# Enclosure_Control.net
KiCad netlist of a schematic drawn in EAGLE
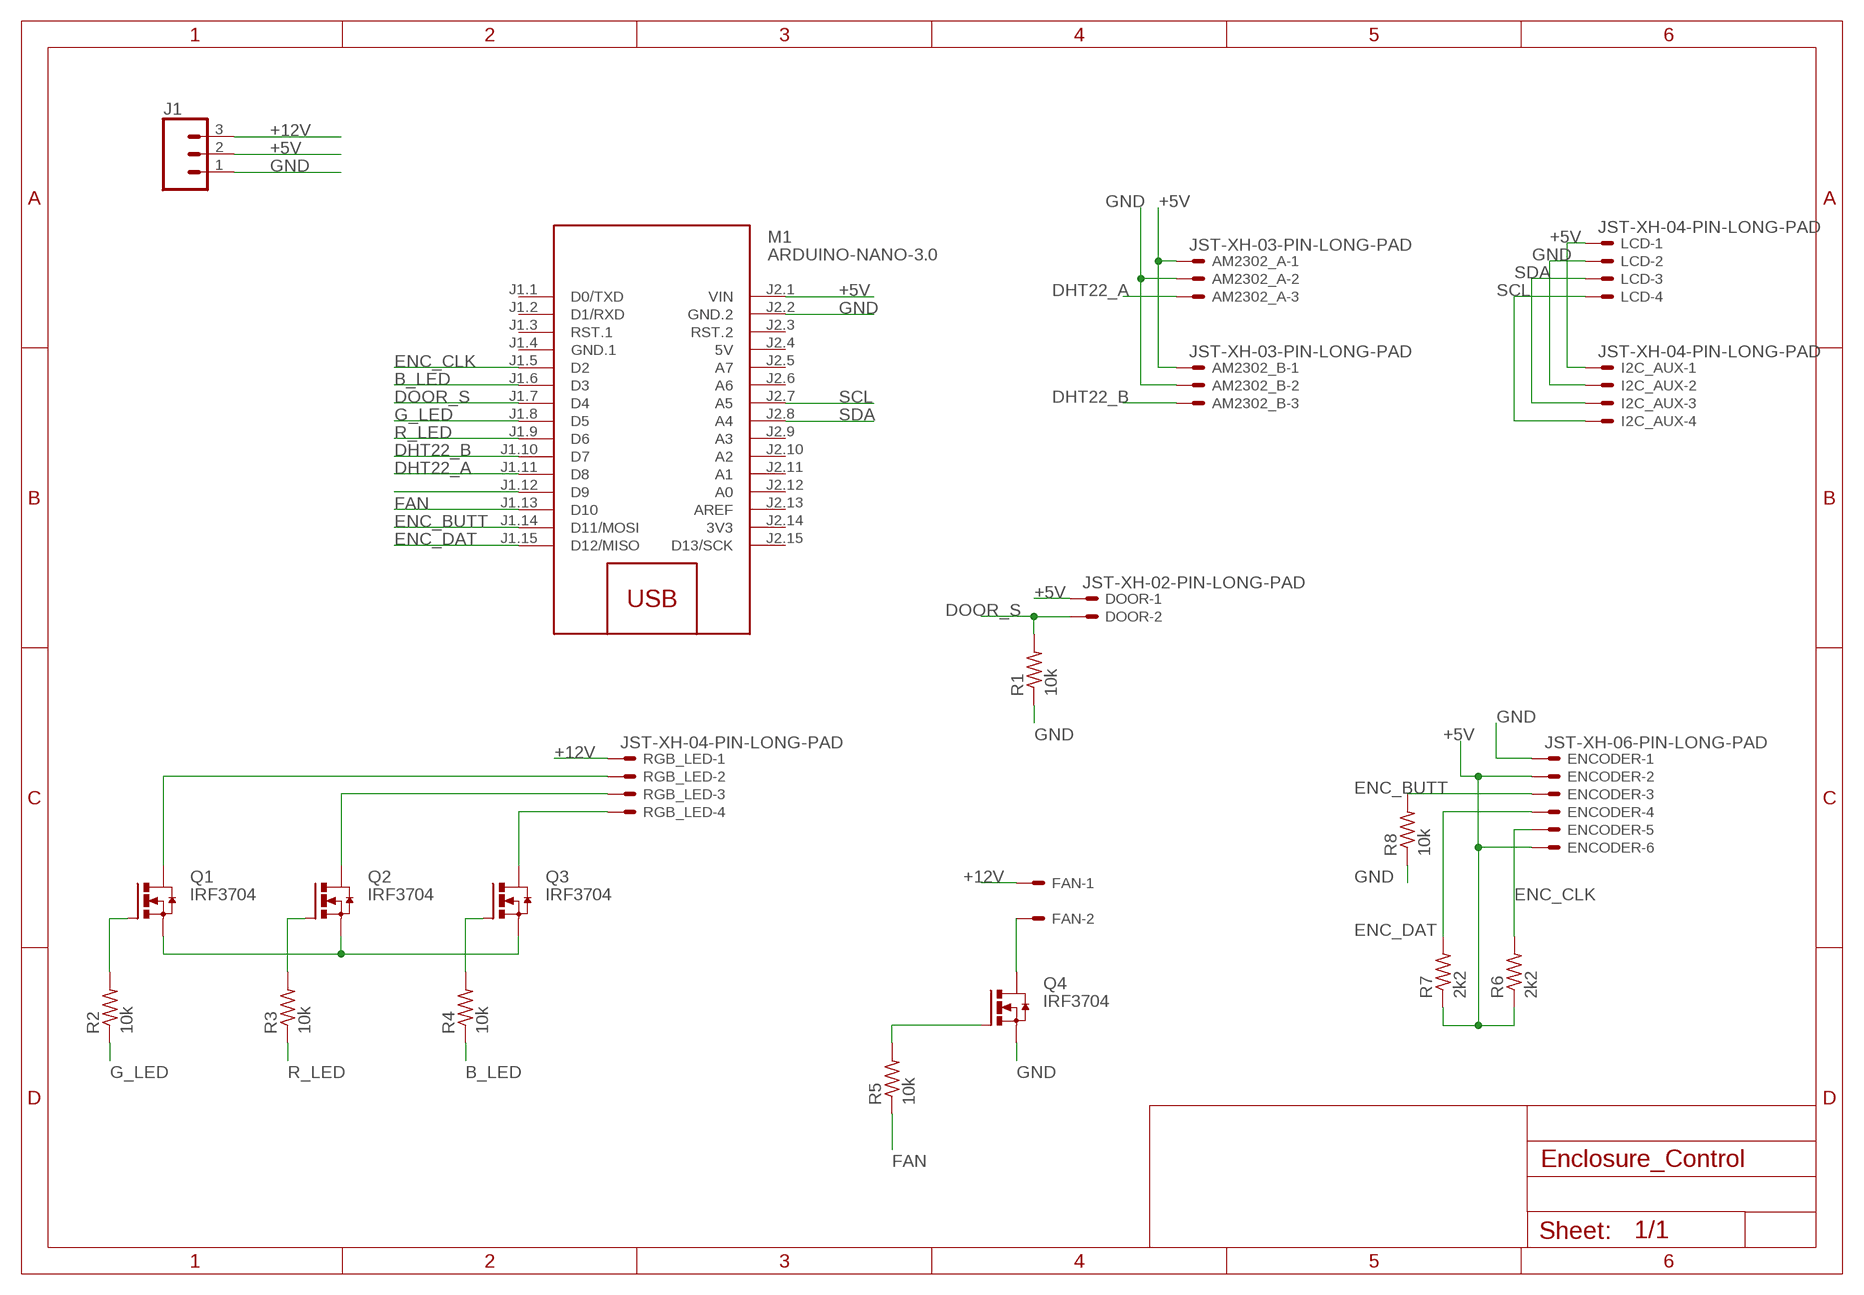
[diagram p0: schematic, sheet 1]

(export (version "E")
  (design (tool "Eeschema 10.0.6"))
  (components
    (comp (ref "AM2302_A")
      (value "JST-XH-03-PIN-LONG-PAD")
      (footprint "eagle-import:JST-XH-03-PACKAGE-LONG-PAD")
      (libsource (lib "eagle-import") (part "JST-XH-03-PIN-LONG-PAD"))
    )
    (comp (ref "AM2302_B")
      (value "JST-XH-03-PIN-LONG-PAD")
      (footprint "eagle-import:JST-XH-03-PACKAGE-LONG-PAD")
      (libsource (lib "eagle-import") (part "JST-XH-03-PIN-LONG-PAD"))
    )
    (comp (ref "DOOR")
      (value "JST-XH-02-PIN-LONG-PAD")
      (footprint "eagle-import:JST-XH-02-PACKAGE-LONG-PAD")
      (libsource (lib "eagle-import") (part "JST-XH-02-PIN-LONG-PAD"))
    )
    (comp (ref "ENCODER")
      (value "JST-XH-06-PIN-LONG-PAD")
      (footprint "eagle-import:JST-XH-06-PACKAGE-LONG-PAD")
      (libsource (lib "eagle-import") (part "JST-XH-06-PIN-LONG-PAD"))
    )
    (comp (ref "FAN")
      (value "KK-156-2")
      (footprint "eagle-import:KK-156-2")
      (fields (field (name "MF") "MOLEX"))
      (libsource (lib "eagle-import") (part "KK-156-2"))
    )
    (comp (ref "I2C_AUX")
      (value "JST-XH-04-PIN-LONG-PAD")
      (footprint "eagle-import:JST-XH-04-PACKAGE-LONG-PAD")
      (libsource (lib "eagle-import") (part "JST-XH-04-PIN-LONG-PAD"))
    )
    (comp (ref "J1")
      (value "CONN_03SCREW-NS")
      (footprint "eagle-import:SCREWTERMINAL-3.5MM-3-NS")
      (libsource (lib "eagle-import") (part "CONN_03SCREW-NS"))
    )
    (comp (ref "LCD")
      (value "JST-XH-04-PIN-LONG-PAD")
      (footprint "eagle-import:JST-XH-04-PACKAGE-LONG-PAD")
      (libsource (lib "eagle-import") (part "JST-XH-04-PIN-LONG-PAD"))
    )
    (comp (ref "M1")
      (value "ARDUINO-NANO-3.0")
      (footprint "eagle-import:ARDUINO-NANO-3.0")
      (libsource (lib "eagle-import") (part "ARDUINO-NANO-3.0"))
    )
    (comp (ref "Q1")
      (value "IRF3704")
      (footprint "eagle-import:TO220AH")
      (libsource (lib "eagle-import") (part "IRF3704"))
    )
    (comp (ref "Q2")
      (value "IRF3704")
      (footprint "eagle-import:TO220AH")
      (libsource (lib "eagle-import") (part "IRF3704"))
    )
    (comp (ref "Q3")
      (value "IRF3704")
      (footprint "eagle-import:TO220AH")
      (libsource (lib "eagle-import") (part "IRF3704"))
    )
    (comp (ref "Q4")
      (value "IRF3704")
      (footprint "eagle-import:TO220AH")
      (libsource (lib "eagle-import") (part "IRF3704"))
    )
    (comp (ref "R1")
      (value "10k")
      (footprint "eagle-import:0309_12")
      (libsource (lib "eagle-import") (part "R-US_0309/12"))
    )
    (comp (ref "R2")
      (value "10k")
      (footprint "eagle-import:0309_12")
      (libsource (lib "eagle-import") (part "R-US_0309/12"))
    )
    (comp (ref "R3")
      (value "10k")
      (footprint "eagle-import:0309_12")
      (libsource (lib "eagle-import") (part "R-US_0309/12"))
    )
    (comp (ref "R4")
      (value "10k")
      (footprint "eagle-import:0309_12")
      (libsource (lib "eagle-import") (part "R-US_0309/12"))
    )
    (comp (ref "R5")
      (value "10k")
      (footprint "eagle-import:0309_12")
      (libsource (lib "eagle-import") (part "R-US_0309/12"))
    )
    (comp (ref "R6")
      (value "2k2")
      (footprint "eagle-import:0309_12")
      (libsource (lib "eagle-import") (part "R-US_0309/12"))
    )
    (comp (ref "R7")
      (value "2k2")
      (footprint "eagle-import:0309_12")
      (libsource (lib "eagle-import") (part "R-US_0309/12"))
    )
    (comp (ref "R8")
      (value "10k")
      (footprint "eagle-import:0309_12")
      (libsource (lib "eagle-import") (part "R-US_0309/12"))
    )
    (comp (ref "RGB_LED")
      (value "JST-XH-04-PIN-LONG-PAD")
      (footprint "eagle-import:JST-XH-04-PACKAGE-LONG-PAD")
      (libsource (lib "eagle-import") (part "JST-XH-04-PIN-LONG-PAD"))
    )
  )
  (nets
    (net (code "1") (name "/+5V") (class "Default")
      (node (ref "AM2302_A") (pin "1") (pinfunction "S_1") (pintype "passive"))
      (node (ref "AM2302_B") (pin "1") (pinfunction "S_1") (pintype "passive"))
      (node (ref "DOOR") (pin "1") (pinfunction "S_1") (pintype "passive"))
      (node (ref "ENCODER") (pin "2") (pinfunction "S_2") (pintype "passive"))
      (node (ref "ENCODER") (pin "6") (pinfunction "S_6") (pintype "passive"))
      (node (ref "I2C_AUX") (pin "1") (pinfunction "S_1") (pintype "passive"))
      (node (ref "J1") (pin "2") (pinfunction "2_2") (pintype "passive"))
      (node (ref "LCD") (pin "1") (pinfunction "S_1") (pintype "passive"))
      (node (ref "M1") (pin "J2.1") (pinfunction "VIN_J2.1") (pintype "power_in"))
      (node (ref "R6") (pin "1") (pinfunction "1_1") (pintype "passive"))
      (node (ref "R7") (pin "1") (pinfunction "1_1") (pintype "passive"))
    )
    (net (code "2") (name "/+12V") (class "Default")
      (node (ref "FAN") (pin "1") (pinfunction "S_1") (pintype "passive"))
      (node (ref "J1") (pin "3") (pinfunction "3_3") (pintype "passive"))
      (node (ref "RGB_LED") (pin "1") (pinfunction "S_1") (pintype "passive"))
    )
    (net (code "3") (name "/3V3") (class "Default")
      (node (ref "M1") (pin "J2.14") (pinfunction "3V3_J2.14") (pintype "power_in"))
    )
    (net (code "4") (name "/5V") (class "Default")
      (node (ref "M1") (pin "J2.4") (pinfunction "5V_J2.4") (pintype "power_in"))
    )
    (net (code "5") (name "/B_LED") (class "Default")
      (node (ref "M1") (pin "J1.6") (pinfunction "D3_J1.6") (pintype "bidirectional"))
      (node (ref "R4") (pin "1") (pinfunction "1_1") (pintype "passive"))
    )
    (net (code "6") (name "/DHT22_A") (class "Default")
      (node (ref "AM2302_A") (pin "3") (pinfunction "S_3") (pintype "passive"))
      (node (ref "M1") (pin "J1.11") (pinfunction "D8_J1.11") (pintype "bidirectional"))
    )
    (net (code "7") (name "/DHT22_B") (class "Default")
      (node (ref "AM2302_B") (pin "3") (pinfunction "S_3") (pintype "passive"))
      (node (ref "M1") (pin "J1.10") (pinfunction "D7_J1.10") (pintype "bidirectional"))
    )
    (net (code "8") (name "/DOOR_S") (class "Default")
      (node (ref "DOOR") (pin "2") (pinfunction "S_2") (pintype "passive"))
      (node (ref "M1") (pin "J1.7") (pinfunction "D4_J1.7") (pintype "bidirectional"))
      (node (ref "R1") (pin "2") (pinfunction "2_2") (pintype "passive"))
    )
    (net (code "9") (name "/ENC_BUTT") (class "Default")
      (node (ref "ENCODER") (pin "3") (pinfunction "S_3") (pintype "passive"))
      (node (ref "M1") (pin "J1.14") (pinfunction "D11/MOSI_J1.14") (pintype "bidirectional"))
      (node (ref "R8") (pin "2") (pinfunction "2_2") (pintype "passive"))
    )
    (net (code "10") (name "/ENC_CLK") (class "Default")
      (node (ref "ENCODER") (pin "5") (pinfunction "S_5") (pintype "passive"))
      (node (ref "M1") (pin "J1.5") (pinfunction "D2_J1.5") (pintype "bidirectional"))
      (node (ref "R6") (pin "2") (pinfunction "2_2") (pintype "passive"))
    )
    (net (code "11") (name "/ENC_DAT") (class "Default")
      (node (ref "ENCODER") (pin "4") (pinfunction "S_4") (pintype "passive"))
      (node (ref "M1") (pin "J1.15") (pinfunction "D12/MISO_J1.15") (pintype "bidirectional"))
      (node (ref "R7") (pin "2") (pinfunction "2_2") (pintype "passive"))
    )
    (net (code "12") (name "/FAN") (class "Default")
      (node (ref "M1") (pin "J1.13") (pinfunction "D10_J1.13") (pintype "bidirectional"))
      (node (ref "R5") (pin "1") (pinfunction "1_1") (pintype "passive"))
    )
    (net (code "13") (name "/GND") (class "Default")
      (node (ref "AM2302_A") (pin "2") (pinfunction "S_2") (pintype "passive"))
      (node (ref "AM2302_B") (pin "2") (pinfunction "S_2") (pintype "passive"))
      (node (ref "ENCODER") (pin "1") (pinfunction "S_1") (pintype "passive"))
      (node (ref "I2C_AUX") (pin "2") (pinfunction "S_2") (pintype "passive"))
      (node (ref "J1") (pin "1") (pinfunction "1_1") (pintype "passive"))
      (node (ref "LCD") (pin "2") (pinfunction "S_2") (pintype "passive"))
      (node (ref "M1") (pin "J2.2") (pinfunction "GND.2_J2.2") (pintype "power_in"))
      (node (ref "Q4") (pin "E") (pinfunction "S_E") (pintype "passive"))
      (node (ref "R1") (pin "1") (pinfunction "1_1") (pintype "passive"))
      (node (ref "R8") (pin "1") (pinfunction "1_1") (pintype "passive"))
    )
    (net (code "14") (name "/GND.1") (class "Default")
      (node (ref "M1") (pin "J1.4") (pinfunction "GND.1_J1.4") (pintype "power_in"))
    )
    (net (code "15") (name "/G_LED") (class "Default")
      (node (ref "M1") (pin "J1.8") (pinfunction "D5_J1.8") (pintype "bidirectional"))
      (node (ref "R2") (pin "1") (pinfunction "1_1") (pintype "passive"))
    )
    (net (code "16") (name "/R_LED") (class "Default")
      (node (ref "M1") (pin "J1.9") (pinfunction "D6_J1.9") (pintype "bidirectional"))
      (node (ref "R3") (pin "1") (pinfunction "1_1") (pintype "passive"))
    )
    (net (code "17") (name "/SCL") (class "Default")
      (node (ref "I2C_AUX") (pin "4") (pinfunction "S_4") (pintype "passive"))
      (node (ref "LCD") (pin "4") (pinfunction "S_4") (pintype "passive"))
      (node (ref "M1") (pin "J2.7") (pinfunction "A5_J2.7") (pintype "bidirectional"))
    )
    (net (code "18") (name "/SDA") (class "Default")
      (node (ref "I2C_AUX") (pin "3") (pinfunction "S_3") (pintype "passive"))
      (node (ref "LCD") (pin "3") (pinfunction "S_3") (pintype "passive"))
      (node (ref "M1") (pin "J2.8") (pinfunction "A4_J2.8") (pintype "bidirectional"))
    )
    (net (code "19") (name "Net-(FANB-S)") (class "Default")
      (node (ref "FAN") (pin "2") (pinfunction "S_2") (pintype "passive"))
      (node (ref "Q4") (pin "C") (pinfunction "D_C") (pintype "passive"))
    )
    (net (code "20") (name "Net-(Q1-D)") (class "Default")
      (node (ref "Q1") (pin "C") (pinfunction "D_C") (pintype "passive"))
      (node (ref "RGB_LED") (pin "2") (pinfunction "S_2") (pintype "passive"))
    )
    (net (code "21") (name "Net-(Q1-G)") (class "Default")
      (node (ref "Q1") (pin "B") (pinfunction "G_B") (pintype "passive"))
      (node (ref "R2") (pin "2") (pinfunction "2_2") (pintype "passive"))
    )
    (net (code "22") (name "Net-(Q1-S)") (class "Default")
      (node (ref "Q1") (pin "E") (pinfunction "S_E") (pintype "passive"))
      (node (ref "Q2") (pin "E") (pinfunction "S_E") (pintype "passive"))
      (node (ref "Q3") (pin "E") (pinfunction "S_E") (pintype "passive"))
    )
    (net (code "23") (name "Net-(Q2-D)") (class "Default")
      (node (ref "Q2") (pin "C") (pinfunction "D_C") (pintype "passive"))
      (node (ref "RGB_LED") (pin "3") (pinfunction "S_3") (pintype "passive"))
    )
    (net (code "24") (name "Net-(Q2-G)") (class "Default")
      (node (ref "Q2") (pin "B") (pinfunction "G_B") (pintype "passive"))
      (node (ref "R3") (pin "2") (pinfunction "2_2") (pintype "passive"))
    )
    (net (code "25") (name "Net-(Q3-D)") (class "Default")
      (node (ref "Q3") (pin "C") (pinfunction "D_C") (pintype "passive"))
      (node (ref "RGB_LED") (pin "4") (pinfunction "S_4") (pintype "passive"))
    )
    (net (code "26") (name "Net-(Q3-G)") (class "Default")
      (node (ref "Q3") (pin "B") (pinfunction "G_B") (pintype "passive"))
      (node (ref "R4") (pin "2") (pinfunction "2_2") (pintype "passive"))
    )
    (net (code "27") (name "Net-(Q4-G)") (class "Default")
      (node (ref "Q4") (pin "B") (pinfunction "G_B") (pintype "passive"))
      (node (ref "R5") (pin "2") (pinfunction "2_2") (pintype "passive"))
    )
    (net (code "28") (name "unconnected-(M1-A0-PadJ2.12)") (class "Default")
      (node (ref "M1") (pin "J2.12") (pinfunction "A0_J2.12") (pintype "bidirectional"))
    )
    (net (code "29") (name "unconnected-(M1-A1-PadJ2.11)") (class "Default")
      (node (ref "M1") (pin "J2.11") (pinfunction "A1_J2.11") (pintype "bidirectional"))
    )
    (net (code "30") (name "unconnected-(M1-A2-PadJ2.10)") (class "Default")
      (node (ref "M1") (pin "J2.10") (pinfunction "A2_J2.10") (pintype "bidirectional"))
    )
    (net (code "31") (name "unconnected-(M1-A3-PadJ2.9)") (class "Default")
      (node (ref "M1") (pin "J2.9") (pinfunction "A3_J2.9") (pintype "bidirectional"))
    )
    (net (code "32") (name "unconnected-(M1-A6-PadJ2.6)") (class "Default")
      (node (ref "M1") (pin "J2.6") (pinfunction "A6_J2.6") (pintype "bidirectional"))
    )
    (net (code "33") (name "unconnected-(M1-A7-PadJ2.5)") (class "Default")
      (node (ref "M1") (pin "J2.5") (pinfunction "A7_J2.5") (pintype "bidirectional"))
    )
    (net (code "34") (name "unconnected-(M1-AREF-PadJ2.13)") (class "Default")
      (node (ref "M1") (pin "J2.13") (pinfunction "AREF_J2.13") (pintype "bidirectional"))
    )
    (net (code "35") (name "unconnected-(M1-D0{slash}TXD-PadJ1.1)") (class "Default")
      (node (ref "M1") (pin "J1.1") (pinfunction "D0/TXD_J1.1") (pintype "bidirectional"))
    )
    (net (code "36") (name "unconnected-(M1-D1{slash}RXD-PadJ1.2)") (class "Default")
      (node (ref "M1") (pin "J1.2") (pinfunction "D1/RXD_J1.2") (pintype "bidirectional"))
    )
    (net (code "37") (name "unconnected-(M1-D9-PadJ1.12)") (class "Default")
      (node (ref "M1") (pin "J1.12") (pinfunction "D9_J1.12") (pintype "bidirectional"))
    )
    (net (code "38") (name "unconnected-(M1-D13{slash}SCK-PadJ2.15)") (class "Default")
      (node (ref "M1") (pin "J2.15") (pinfunction "D13/SCK_J2.15") (pintype "bidirectional"))
    )
    (net (code "39") (name "unconnected-(M1-RST.1-PadJ1.3)") (class "Default")
      (node (ref "M1") (pin "J1.3") (pinfunction "RST.1_J1.3") (pintype "bidirectional"))
    )
    (net (code "40") (name "unconnected-(M1-RST.2-PadJ2.3)") (class "Default")
      (node (ref "M1") (pin "J2.3") (pinfunction "RST.2_J2.3") (pintype "bidirectional"))
    )
  )
)
